# Connectors.net
KiCad netlist of a schematic drawn in Altium Designer
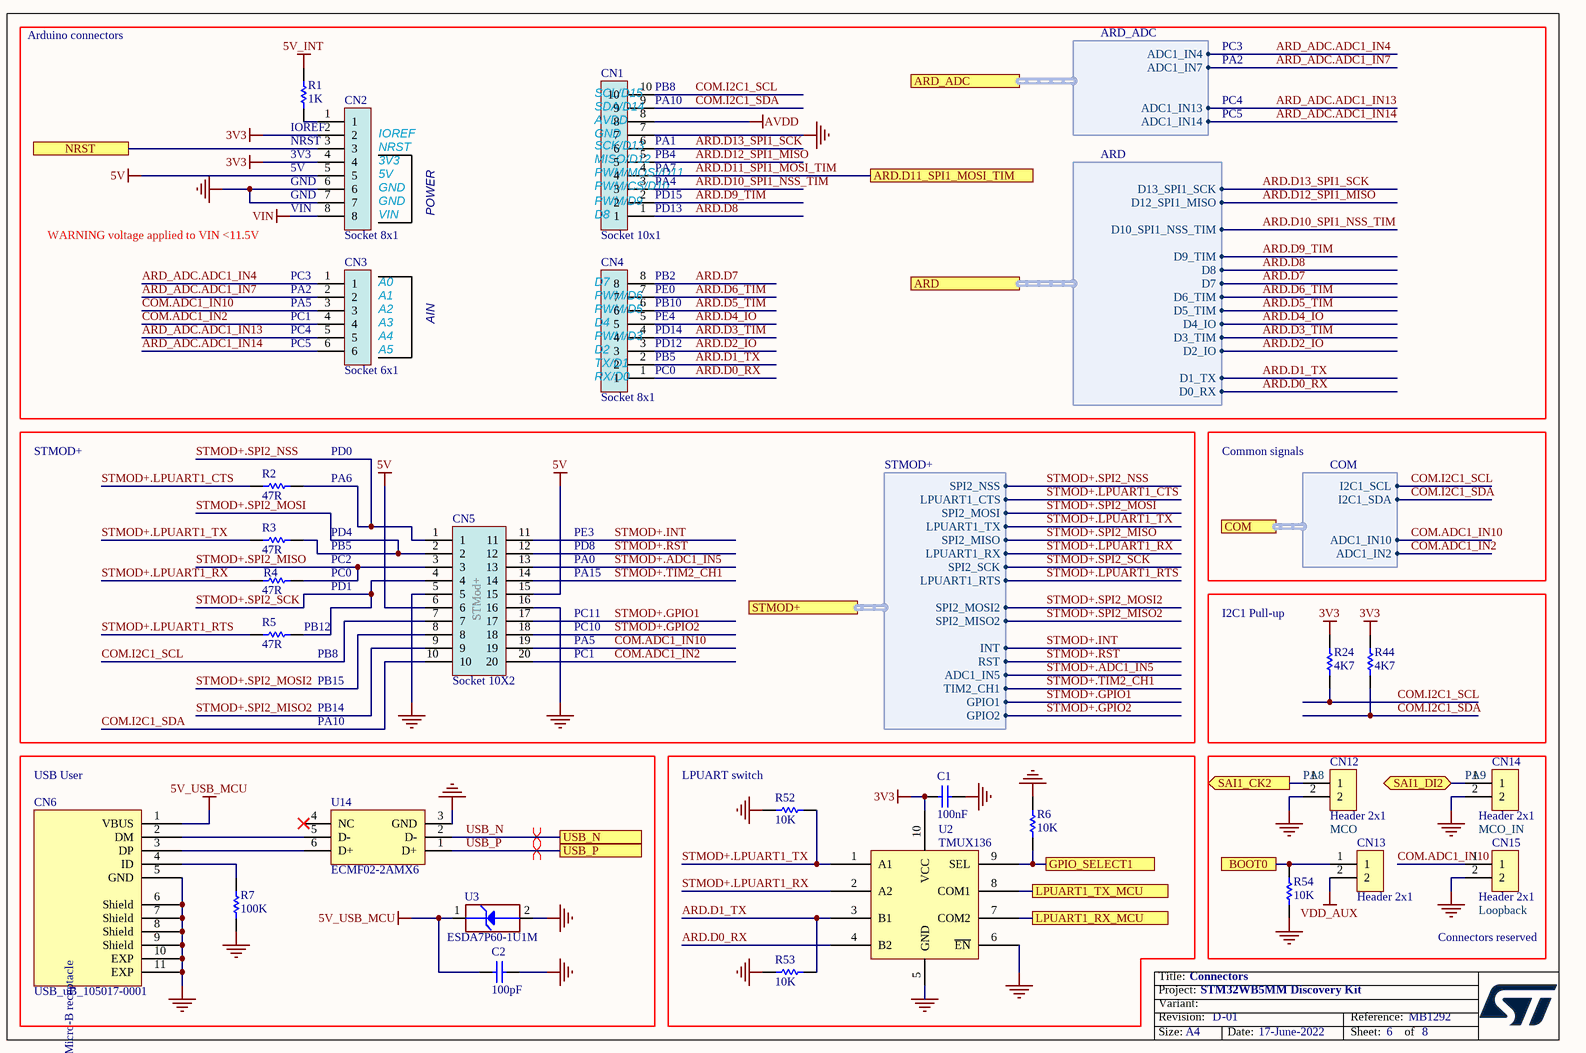
[diagram p0: Connectors.SchDoc]

(export (version "E")
  (design (tool "Eeschema 10.0.6"))
  (components
    (comp (ref "C1")
      (value "100nF")
      (footprint "C0603")
      (description "Capacitor, MLCC, 100nF, 6V3, X5R, 10%, 0603, T=0,8mm")
      (fields (field (name "INTERNAL_PART_NUMBER") "MCD-02119") (field (name "MANUFACTURER") "KEMET"))
      (libsource (lib "MCD_PARTS_database") (part "Capacitor"))
    )
    (comp (ref "C2")
      (value "100pF")
      (footprint "C0603_H0P8")
      (description "Capacitor,MLCC,100pF 50V,NPO,+/-5%, 0603,T=0,8mm")
      (fields
        (field (name "INTERNAL_PART_NUMBER") "MCD-01648")
        (field (name "MANUFACTURER_PART_NUMBER") "CC0603JRNPO9BN101")
      )
      (libsource (lib "MCD_PARTS_database") (part "Capacitor"))
    )
    (comp (ref "CN1")
      (value "Socket 10x1")
      (footprint "CON_SAMTEC_SSW-110-22-X-S-VS")
      (description "Socket, 10x1, 2.54mm, VR, SMT, Height 9.78mm")
      (fields
        (field (name "INTERNAL_PART_NUMBER") "MCD-00301")
        (field (name "MANUFACTURER_PART_NUMBER") "SSW-110-22-L-S-VS")
      )
      (libsource (lib "MCD_PARTS_database") (part "Socket 10x1"))
    )
    (comp (ref "CN2")
      (value "Socket 8x1")
      (footprint "CON_SAMTEC_SSW-108-22-X-S-VS")
      (description "Socket, 8x1, 2.54mm, VR, SMT, Height 9.78mm")
      (fields
        (field (name "INTERNAL_PART_NUMBER") "MCD-00300")
        (field (name "MANUFACTURER_PART_NUMBER") "SSW-108-22-L-S-VS")
      )
      (libsource (lib "MCD_PARTS_database") (part "Socket 8x1"))
    )
    (comp (ref "CN3")
      (value "Socket 6x1")
      (footprint "CON_SAMTEC_SSW-106-22-X-S-VS")
      (description "Socket, 6x1, 2.54mm, VR, SMT, Height 9.78mm")
      (fields
        (field (name "INTERNAL_PART_NUMBER") "MCD-00299")
        (field (name "MANUFACTURER_PART_NUMBER") "SSW-106-22-L-S-VS")
      )
      (libsource (lib "MCD_PARTS_database") (part "Socket 6x1"))
    )
    (comp (ref "CN4")
      (value "Socket 8x1")
      (footprint "CON_SAMTEC_SSW-108-22-X-S-VS")
      (description "Socket, 8x1, 2.54mm, VR, SMT, Height 9.78mm")
      (fields
        (field (name "INTERNAL_PART_NUMBER") "MCD-00300")
        (field (name "MANUFACTURER_PART_NUMBER") "SSW-108-22-L-S-VS")
      )
      (libsource (lib "") (part "Socket 8x1_1"))
    )
    (comp (ref "CN5")
      (value "Socket 10X2")
      (footprint "CON_SAMTEC_SQT-110-01-F-D-RA__STMOD+")
      (description "Socket, 10x2, 2mm, RA, TH, T=6.35mm/2.29mm")
      (fields (field (name "INTERNAL_PART_NUMBER") "MCD-00309") (field (name "MANUFACTURER") "SAMTEC"))
      (libsource (lib "MCD_PARTS_database") (part "Socket 10X2 STMod+"))
    )
    (comp (ref "CN6")
      (value "USB_uB_105017-0001")
      (footprint "CON_USBMICROB_MOLEX_105017-0001_H2P90")
      (description "USB-MICRO-B, 0.65mm, RA, SMT, Bottom Mount,")
      (fields
        (field (name "INTERNAL_PART_NUMBER") "MCD-00028")
        (field (name "MANUFACTURER_PART_NUMBER") "1050170001")
      )
      (libsource (lib "MCD_PARTS_database") (part "USB_uB_105017.0001"))
    )
    (comp (ref "CN12")
      (value "Header 2x1")
      (footprint "CON_LYCONN_313102S141346")
      (description "Header 2x1, 2.54mm, VR, TH, height 5.84mm/5.08 mm, height total 13.46 mm")
      (fields
        (field (name "INTERNAL_PART_NUMBER") "MCD-01668")
        (field (name "MANUFACTURER_PART_NUMBER") "313102S141346")
      )
      (libsource (lib "MCD_PARTS_database") (part "Header 2x1"))
    )
    (comp (ref "CN13")
      (value "Header 2x1")
      (footprint "CON_LYCONN_313102S141346")
      (description "Header 2x1, 2.54mm, VR, TH, height 5.84mm/5.08 mm, height total 13.46 mm")
      (fields
        (field (name "INTERNAL_PART_NUMBER") "MCD-01668")
        (field (name "MANUFACTURER_PART_NUMBER") "313102S141346")
      )
      (libsource (lib "MCD_PARTS_database") (part "Header 2x1"))
    )
    (comp (ref "CN14")
      (value "Header 2x1")
      (footprint "CON_LYCONN_313102S141346")
      (description "Header 2x1, 2.54mm, VR, TH, height 5.84mm/5.08 mm, height total 13.46 mm")
      (fields
        (field (name "INTERNAL_PART_NUMBER") "MCD-01668")
        (field (name "MANUFACTURER_PART_NUMBER") "313102S141346")
      )
      (libsource (lib "MCD_PARTS_database") (part "Header 2x1"))
    )
    (comp (ref "CN15")
      (value "Header 2x1")
      (footprint "CON_LYCONN_313102S141346")
      (description "Header 2x1, 2.54mm, VR, TH, height 5.84mm/5.08 mm, height total 13.46 mm")
      (fields
        (field (name "INTERNAL_PART_NUMBER") "MCD-01668")
        (field (name "MANUFACTURER_PART_NUMBER") "313102S141346")
      )
      (libsource (lib "MCD_PARTS_database") (part "Header 2x1"))
    )
    (comp (ref "R1")
      (value "1K")
      (footprint "R0402")
      (description "Resistor,1K,0402,1%,1/16W")
      (fields
        (field (name "INTERNAL_PART_NUMBER") "MCD-00061")
        (field (name "MANUFACTURER_PART_NUMBER") "RC0402FR-071KL")
      )
      (libsource (lib "MCD_PARTS_database") (part "Resistor"))
    )
    (comp (ref "R2")
      (value "47R")
      (footprint "R0402")
      (description "Resistor,47R,0402,1%,1/16W")
      (fields
        (field (name "INTERNAL_PART_NUMBER") "MCD-00481")
        (field (name "MANUFACTURER_PART_NUMBER") "RC0402FR-0747RL")
      )
      (libsource (lib "MCD_PARTS_database") (part "Resistor"))
    )
    (comp (ref "R3")
      (value "47R")
      (footprint "R0402")
      (description "Resistor,47R,0402,1%,1/16W")
      (fields
        (field (name "INTERNAL_PART_NUMBER") "MCD-00481")
        (field (name "MANUFACTURER_PART_NUMBER") "RC0402FR-0747RL")
      )
      (libsource (lib "MCD_PARTS_database") (part "Resistor"))
    )
    (comp (ref "R4")
      (value "47R")
      (footprint "R0402")
      (description "Resistor,47R,0402,1%,1/16W")
      (fields
        (field (name "INTERNAL_PART_NUMBER") "MCD-00481")
        (field (name "MANUFACTURER_PART_NUMBER") "RC0402FR-0747RL")
      )
      (libsource (lib "MCD_PARTS_database") (part "Resistor"))
    )
    (comp (ref "R5")
      (value "47R")
      (footprint "R0402")
      (description "Resistor,47R,0402,1%,1/16W")
      (fields
        (field (name "INTERNAL_PART_NUMBER") "MCD-00481")
        (field (name "MANUFACTURER_PART_NUMBER") "RC0402FR-0747RL")
      )
      (libsource (lib "MCD_PARTS_database") (part "Resistor"))
    )
    (comp (ref "R6")
      (value "10K")
      (footprint "R0402")
      (description "Resistor,10K,0402,1%,1/16W")
      (fields
        (field (name "INTERNAL_PART_NUMBER") "MCD-00053")
        (field (name "MANUFACTURER_PART_NUMBER") "RC0402FR-0710KL")
      )
      (libsource (lib "MCD_PARTS_database") (part "Resistor"))
    )
    (comp (ref "R7")
      (value "100K")
      (footprint "R0402")
      (description "Resistor,100K,0402,1%,1/16W")
      (fields
        (field (name "INTERNAL_PART_NUMBER") "MCD-00059")
        (field (name "MANUFACTURER_PART_NUMBER") "RC0402FR-07100KL")
      )
      (libsource (lib "MCD_PARTS_database") (part "Resistor"))
    )
    (comp (ref "R24")
      (value "4K7")
      (footprint "R0603")
      (description "Resistor,4K7,0603,1%,1/10W")
      (fields
        (field (name "INTERNAL_PART_NUMBER") "MCD-00219")
        (field (name "MANUFACTURER_PART_NUMBER") "RC0603FR-074K7L")
      )
      (libsource (lib "MCD_PARTS_database") (part "Resistor"))
    )
    (comp (ref "R44")
      (value "4K7")
      (footprint "R0603")
      (description "Resistor,4K7,0603,1%,1/10W")
      (fields
        (field (name "INTERNAL_PART_NUMBER") "MCD-00219")
        (field (name "MANUFACTURER_PART_NUMBER") "RC0603FR-074K7L")
      )
      (libsource (lib "MCD_PARTS_database") (part "Resistor"))
    )
    (comp (ref "R52")
      (value "10K")
      (footprint "R0402")
      (description "Resistor,10K,0402,1%,1/16W")
      (fields
        (field (name "INTERNAL_PART_NUMBER") "MCD-00053")
        (field (name "MANUFACTURER_PART_NUMBER") "RC0402FR-0710KL")
      )
      (libsource (lib "MCD_PARTS_database") (part "Resistor"))
    )
    (comp (ref "R53")
      (value "10K")
      (footprint "R0402")
      (description "Resistor,10K,0402,1%,1/16W")
      (fields
        (field (name "INTERNAL_PART_NUMBER") "MCD-00053")
        (field (name "MANUFACTURER_PART_NUMBER") "RC0402FR-0710KL")
      )
      (libsource (lib "MCD_PARTS_database") (part "Resistor"))
    )
    (comp (ref "R54")
      (value "10K")
      (footprint "R0402")
      (description "Resistor,10K,0402,1%,1/16W")
      (fields
        (field (name "INTERNAL_PART_NUMBER") "MCD-00053")
        (field (name "MANUFACTURER_PART_NUMBER") "RC0402FR-0710KL")
      )
      (libsource (lib "MCD_PARTS_database") (part "Resistor"))
    )
    (comp (ref "U2")
      (value "TMUX136")
      (footprint "ICC_UQFN10_RSE_R-PUQFN-N10_1P5X2_P050")
      (description "6-GHz, 2-Channel, 2:1 Switch, With Power-off Isolation")
      (fields
        (field (name "INTERNAL_PART_NUMBER") "MCD-01847")
        (field (name "MANUFACTURER") "TEXAS INSTRUMENTS")
      )
      (libsource (lib "MCD_PARTS_database") (part "TMUX136"))
    )
    (comp (ref "U3")
      (value "ESDA7P60-1U1M")
      (footprint "ESD_QFN2_1P6X1_P125")
      (description "High power transient voltage suppressor, 7V breakdown")
      (fields
        (field (name "INTERNAL_PART_NUMBER") "MCD-00251")
        (field (name "MANUFACTURER") "STMICROELECTRONICS")
      )
      (libsource (lib "MCD_PARTS_database") (part "ESD-TRANSIL"))
    )
    (comp (ref "U14")
      (value "ECMF02-2AMX6")
      (footprint "ESD_QFN-6L_1P7X1P5_P050")
      (description "Common mode filter with ESD protection for USB 2.0 interface")
      (fields
        (field (name "INTERNAL_PART_NUMBER") "MCD-00649")
        (field (name "MANUFACTURER") "STMICROELECTRONICS")
      )
      (libsource (lib "MCD_PARTS_database") (part "ECMF02-2AMX6"))
    )
  )
  (nets
    (net (code "5") (name "/ARD.D0_RX") (class "Default")
      (node (ref "CN4") (pin "1") (pinfunction "1_1") (pintype "passive"))
      (node (ref "U2") (pin "4") (pinfunction "B2_4") (pintype "passive"))
    )
    (net (code "6") (name "/ARD.D1_TX") (class "Default")
      (node (ref "CN4") (pin "2") (pinfunction "2_2") (pintype "passive"))
      (node (ref "R53") (pin "2") (pinfunction "2_2") (pintype "passive"))
      (node (ref "U2") (pin "3") (pinfunction "B1_3") (pintype "passive"))
    )
    (net (code "7") (name "/ARD.D2_IO") (class "Default")
      (node (ref "CN4") (pin "3") (pinfunction "3_3") (pintype "passive"))
    )
    (net (code "8") (name "/ARD.D3_TIM") (class "Default")
      (node (ref "CN4") (pin "4") (pinfunction "4_4") (pintype "passive"))
    )
    (net (code "9") (name "/ARD.D4_IO") (class "Default")
      (node (ref "CN4") (pin "5") (pinfunction "5_5") (pintype "passive"))
    )
    (net (code "10") (name "/ARD.D5_TIM") (class "Default")
      (node (ref "CN4") (pin "6") (pinfunction "6_6") (pintype "passive"))
    )
    (net (code "11") (name "/ARD.D6_TIM") (class "Default")
      (node (ref "CN4") (pin "7") (pinfunction "7_7") (pintype "passive"))
    )
    (net (code "12") (name "/ARD.D7") (class "Default")
      (node (ref "CN4") (pin "8") (pinfunction "8_8") (pintype "passive"))
    )
    (net (code "13") (name "/ARD.D8") (class "Default")
      (node (ref "CN1") (pin "1") (pinfunction "1_1") (pintype "passive"))
    )
    (net (code "14") (name "/ARD.D9_TIM") (class "Default")
      (node (ref "CN1") (pin "2") (pinfunction "2_2") (pintype "passive"))
    )
    (net (code "15") (name "/ARD.D10_SPI1_NSS_TIM") (class "Default")
      (node (ref "CN1") (pin "3") (pinfunction "3_3") (pintype "passive"))
    )
    (net (code "16") (name "/ARD.D11_SPI1_MOSI_TIM") (class "Default")
      (node (ref "CN1") (pin "4") (pinfunction "4_4") (pintype "passive"))
    )
    (net (code "17") (name "/ARD.D12_SPI1_MISO") (class "Default")
      (node (ref "CN1") (pin "5") (pinfunction "5_5") (pintype "passive"))
    )
    (net (code "18") (name "/ARD.D13_SPI1_SCK") (class "Default")
      (node (ref "CN1") (pin "6") (pinfunction "6_6") (pintype "passive"))
    )
    (net (code "19") (name "/ARD_ADC.ADC1_IN4") (class "Default")
      (node (ref "CN3") (pin "1") (pinfunction "1_1") (pintype "passive"))
    )
    (net (code "20") (name "/ARD_ADC.ADC1_IN7") (class "Default")
      (node (ref "CN3") (pin "2") (pinfunction "2_2") (pintype "passive"))
    )
    (net (code "21") (name "/ARD_ADC.ADC1_IN13") (class "Default")
      (node (ref "CN3") (pin "5") (pinfunction "5_5") (pintype "passive"))
    )
    (net (code "22") (name "/ARD_ADC.ADC1_IN14") (class "Default")
      (node (ref "CN3") (pin "6") (pinfunction "6_6") (pintype "passive"))
    )
    (net (code "23") (name "/BOOT0") (class "Default")
      (node (ref "CN13") (pin "1") (pinfunction "1_1") (pintype "passive"))
      (node (ref "R54") (pin "2") (pinfunction "2_2") (pintype "passive"))
    )
    (net (code "24") (name "/COM.ADC1_IN2") (class "Default")
      (node (ref "CN3") (pin "4") (pinfunction "4_4") (pintype "passive"))
      (node (ref "CN5") (pin "20") (pinfunction "20_20") (pintype "passive"))
    )
    (net (code "25") (name "/COM.ADC1_IN10") (class "Default")
      (node (ref "CN15") (pin "1") (pinfunction "1_1") (pintype "passive"))
      (node (ref "CN3") (pin "3") (pinfunction "3_3") (pintype "passive"))
      (node (ref "CN5") (pin "19") (pinfunction "19_19") (pintype "passive"))
    )
    (net (code "26") (name "/COM.I2C1_SCL") (class "Default")
      (node (ref "CN1") (pin "10") (pinfunction "10_10") (pintype "passive"))
      (node (ref "CN5") (pin "7") (pinfunction "7_7") (pintype "passive"))
      (node (ref "R24") (pin "1") (pinfunction "1_1") (pintype "passive"))
    )
    (net (code "27") (name "/COM.I2C1_SDA") (class "Default")
      (node (ref "CN1") (pin "9") (pinfunction "9_9") (pintype "passive"))
      (node (ref "CN5") (pin "10") (pinfunction "10_10") (pintype "passive"))
      (node (ref "R44") (pin "1") (pinfunction "1_1") (pintype "passive"))
    )
    (net (code "28") (name "/GPIO_SELECT1") (class "Default")
      (node (ref "R6") (pin "1") (pinfunction "1_1") (pintype "passive"))
      (node (ref "U2") (pin "9") (pinfunction "SEL_9") (pintype "passive"))
    )
    (net (code "29") (name "/LPUART1_RX_MCU") (class "Default")
      (node (ref "U2") (pin "7") (pinfunction "COM2_7") (pintype "passive"))
    )
    (net (code "30") (name "/LPUART1_TX_MCU") (class "Default")
      (node (ref "U2") (pin "8") (pinfunction "COM1_8") (pintype "passive"))
    )
    (net (code "31") (name "/NRST") (class "Default")
      (node (ref "CN2") (pin "3") (pinfunction "3_3") (pintype "passive"))
    )
    (net (code "32") (name "/SAI1_CK2") (class "Default")
      (node (ref "CN12") (pin "1") (pinfunction "1_1") (pintype "passive"))
    )
    (net (code "33") (name "/SAI1_DI2") (class "Default")
      (node (ref "CN14") (pin "1") (pinfunction "1_1") (pintype "passive"))
    )
    (net (code "34") (name "/STMOD+.ADC1_IN5") (class "Default")
      (node (ref "CN5") (pin "13") (pinfunction "13_13") (pintype "passive"))
    )
    (net (code "35") (name "/STMOD+.GPIO1") (class "Default")
      (node (ref "CN5") (pin "17") (pinfunction "17_17") (pintype "passive"))
    )
    (net (code "36") (name "/STMOD+.GPIO2") (class "Default")
      (node (ref "CN5") (pin "18") (pinfunction "18_18") (pintype "passive"))
    )
    (net (code "37") (name "/STMOD+.INT") (class "Default")
      (node (ref "CN5") (pin "11") (pinfunction "11_11") (pintype "passive"))
    )
    (net (code "38") (name "/STMOD+.LPUART1_CTS") (class "Default")
      (node (ref "R2") (pin "1") (pinfunction "1_1") (pintype "passive"))
    )
    (net (code "39") (name "/STMOD+.LPUART1_RTS") (class "Default")
      (node (ref "R5") (pin "1") (pinfunction "1_1") (pintype "passive"))
    )
    (net (code "40") (name "/STMOD+.LPUART1_RX") (class "Default")
      (node (ref "R4") (pin "1") (pinfunction "1_1") (pintype "passive"))
      (node (ref "U2") (pin "2") (pinfunction "A2_2") (pintype "passive"))
    )
    (net (code "41") (name "/STMOD+.LPUART1_TX") (class "Default")
      (node (ref "R3") (pin "1") (pinfunction "1_1") (pintype "passive"))
      (node (ref "R52") (pin "2") (pinfunction "2_2") (pintype "passive"))
      (node (ref "U2") (pin "1") (pinfunction "A1_1") (pintype "passive"))
    )
    (net (code "42") (name "/STMOD+.RST") (class "Default")
      (node (ref "CN5") (pin "12") (pinfunction "12_12") (pintype "passive"))
    )
    (net (code "43") (name "/STMOD+.SPI2_MISO") (class "Default")
      (node (ref "CN5") (pin "3") (pinfunction "3_3") (pintype "passive"))
      (node (ref "R4") (pin "2") (pinfunction "2_2") (pintype "passive"))
    )
    (net (code "44") (name "/STMOD+.SPI2_MISO2") (class "Default")
      (node (ref "CN5") (pin "9") (pinfunction "9_9") (pintype "passive"))
    )
    (net (code "45") (name "/STMOD+.SPI2_MOSI") (class "Default")
      (node (ref "CN5") (pin "2") (pinfunction "2_2") (pintype "passive"))
      (node (ref "R3") (pin "2") (pinfunction "2_2") (pintype "passive"))
    )
    (net (code "46") (name "/STMOD+.SPI2_MOSI2") (class "Default")
      (node (ref "CN5") (pin "8") (pinfunction "8_8") (pintype "passive"))
    )
    (net (code "47") (name "/STMOD+.SPI2_NSS") (class "Default")
      (node (ref "CN5") (pin "1") (pinfunction "1_1") (pintype "passive"))
      (node (ref "R2") (pin "2") (pinfunction "2_2") (pintype "passive"))
    )
    (net (code "48") (name "/STMOD+.SPI2_SCK") (class "Default")
      (node (ref "CN5") (pin "4") (pinfunction "4_4") (pintype "passive"))
      (node (ref "R5") (pin "2") (pinfunction "2_2") (pintype "passive"))
    )
    (net (code "49") (name "/STMOD+.TIM2_CH1") (class "Default")
      (node (ref "CN5") (pin "14") (pinfunction "14_14") (pintype "passive"))
    )
    (net (code "50") (name "/USB_N") (class "Default")
      (node (ref "U14") (pin "2") (pinfunction "D-_2") (pintype "passive"))
    )
    (net (code "51") (name "/USB_P") (class "Default")
      (node (ref "U14") (pin "1") (pinfunction "D+_1") (pintype "passive"))
    )
    (net (code "56") (name "3V3") (class "Default")
      (node (ref "C1") (pin "2") (pinfunction "2_2") (pintype "passive"))
      (node (ref "CN2") (pin "2") (pinfunction "2_2") (pintype "passive"))
      (node (ref "CN2") (pin "4") (pinfunction "4_4") (pintype "passive"))
      (node (ref "R24") (pin "2") (pinfunction "2_2") (pintype "passive"))
      (node (ref "R44") (pin "2") (pinfunction "2_2") (pintype "passive"))
      (node (ref "U2") (pin "10") (pinfunction "VCC_10") (pintype "power_in"))
    )
    (net (code "57") (name "5V") (class "Default")
      (node (ref "CN2") (pin "5") (pinfunction "5_5") (pintype "passive"))
      (node (ref "CN5") (pin "15") (pinfunction "15_15") (pintype "passive"))
      (node (ref "CN5") (pin "6") (pinfunction "6_6") (pintype "passive"))
    )
    (net (code "58") (name "5V_INT") (class "Default")
      (node (ref "R1") (pin "2") (pinfunction "2_2") (pintype "passive"))
    )
    (net (code "59") (name "5V_USB_MCU") (class "Default")
      (node (ref "C2") (pin "1") (pinfunction "1_1") (pintype "passive"))
      (node (ref "CN6") (pin "1") (pinfunction "VBUS_1") (pintype "passive"))
      (node (ref "U3") (pin "1") (pinfunction "IO1_1") (pintype "passive"))
    )
    (net (code "60") (name "AVDD") (class "Default")
      (node (ref "CN1") (pin "8") (pinfunction "8_8") (pintype "passive"))
    )
    (net (code "61") (name "GND") (class "Default")
      (node (ref "C1") (pin "1") (pinfunction "1_1") (pintype "passive"))
      (node (ref "C2") (pin "2") (pinfunction "2_2") (pintype "passive"))
      (node (ref "CN1") (pin "7") (pinfunction "7_7") (pintype "passive"))
      (node (ref "CN12") (pin "2") (pinfunction "2_2") (pintype "passive"))
      (node (ref "CN14") (pin "2") (pinfunction "2_2") (pintype "passive"))
      (node (ref "CN15") (pin "2") (pinfunction "2_2") (pintype "passive"))
      (node (ref "CN2") (pin "6") (pinfunction "6_6") (pintype "passive"))
      (node (ref "CN2") (pin "7") (pinfunction "7_7") (pintype "passive"))
      (node (ref "CN5") (pin "16") (pinfunction "16_16") (pintype "passive"))
      (node (ref "CN5") (pin "5") (pinfunction "5_5") (pintype "passive"))
      (node (ref "CN6") (pin "10") (pinfunction "EXP_10") (pintype "passive"))
      (node (ref "CN6") (pin "11") (pinfunction "EXP_11") (pintype "passive"))
      (node (ref "CN6") (pin "5") (pinfunction "GND_5") (pintype "passive"))
      (node (ref "CN6") (pin "6") (pinfunction "Shield_6") (pintype "passive"))
      (node (ref "CN6") (pin "7") (pinfunction "Shield_7") (pintype "passive"))
      (node (ref "CN6") (pin "8") (pinfunction "Shield_8") (pintype "passive"))
      (node (ref "CN6") (pin "9") (pinfunction "Shield_9") (pintype "passive"))
      (node (ref "R52") (pin "1") (pinfunction "1_1") (pintype "passive"))
      (node (ref "R53") (pin "1") (pinfunction "1_1") (pintype "passive"))
      (node (ref "R54") (pin "1") (pinfunction "1_1") (pintype "passive"))
      (node (ref "R6") (pin "2") (pinfunction "2_2") (pintype "passive"))
      (node (ref "R7") (pin "1") (pinfunction "1_1") (pintype "passive"))
      (node (ref "U14") (pin "3") (pinfunction "GND_3") (pintype "passive"))
      (node (ref "U2") (pin "5") (pinfunction "GND_5") (pintype "passive"))
      (node (ref "U2") (pin "6") (pinfunction "~{EN}_6") (pintype "passive"))
      (node (ref "U3") (pin "2") (pinfunction "GND_2") (pintype "passive"))
    )
    (net (code "62") (name "Net-(CN2-Pad1)") (class "Default")
      (node (ref "CN2") (pin "1") (pinfunction "1_1") (pintype "passive"))
      (node (ref "R1") (pin "1") (pinfunction "1_1") (pintype "passive"))
    )
    (net (code "63") (name "Net-(CN6-DM)") (class "Default")
      (node (ref "CN6") (pin "2") (pinfunction "DM_2") (pintype "passive"))
      (node (ref "U14") (pin "5") (pinfunction "D-_5") (pintype "passive"))
    )
    (net (code "64") (name "Net-(CN6-DP)") (class "Default")
      (node (ref "CN6") (pin "3") (pinfunction "DP_3") (pintype "passive"))
      (node (ref "U14") (pin "6") (pinfunction "D+_6") (pintype "passive"))
    )
    (net (code "65") (name "Net-(CN6-ID)") (class "Default")
      (node (ref "CN6") (pin "4") (pinfunction "ID_4") (pintype "passive"))
      (node (ref "R7") (pin "2") (pinfunction "2_2") (pintype "passive"))
    )
    (net (code "66") (name "VDD_AUX") (class "Default")
      (node (ref "CN13") (pin "2") (pinfunction "2_2") (pintype "passive"))
    )
    (net (code "67") (name "VIN") (class "Default")
      (node (ref "CN2") (pin "8") (pinfunction "8_8") (pintype "passive"))
    )
    (net (code "68") (name "unconnected-(U14-NC-Pad4)") (class "Default")
      (node (ref "U14") (pin "4") (pinfunction "NC_4") (pintype "passive+no_connect"))
    )
  )
)
